# MCU.net
KiCad netlist of a schematic drawn in Altium Designer
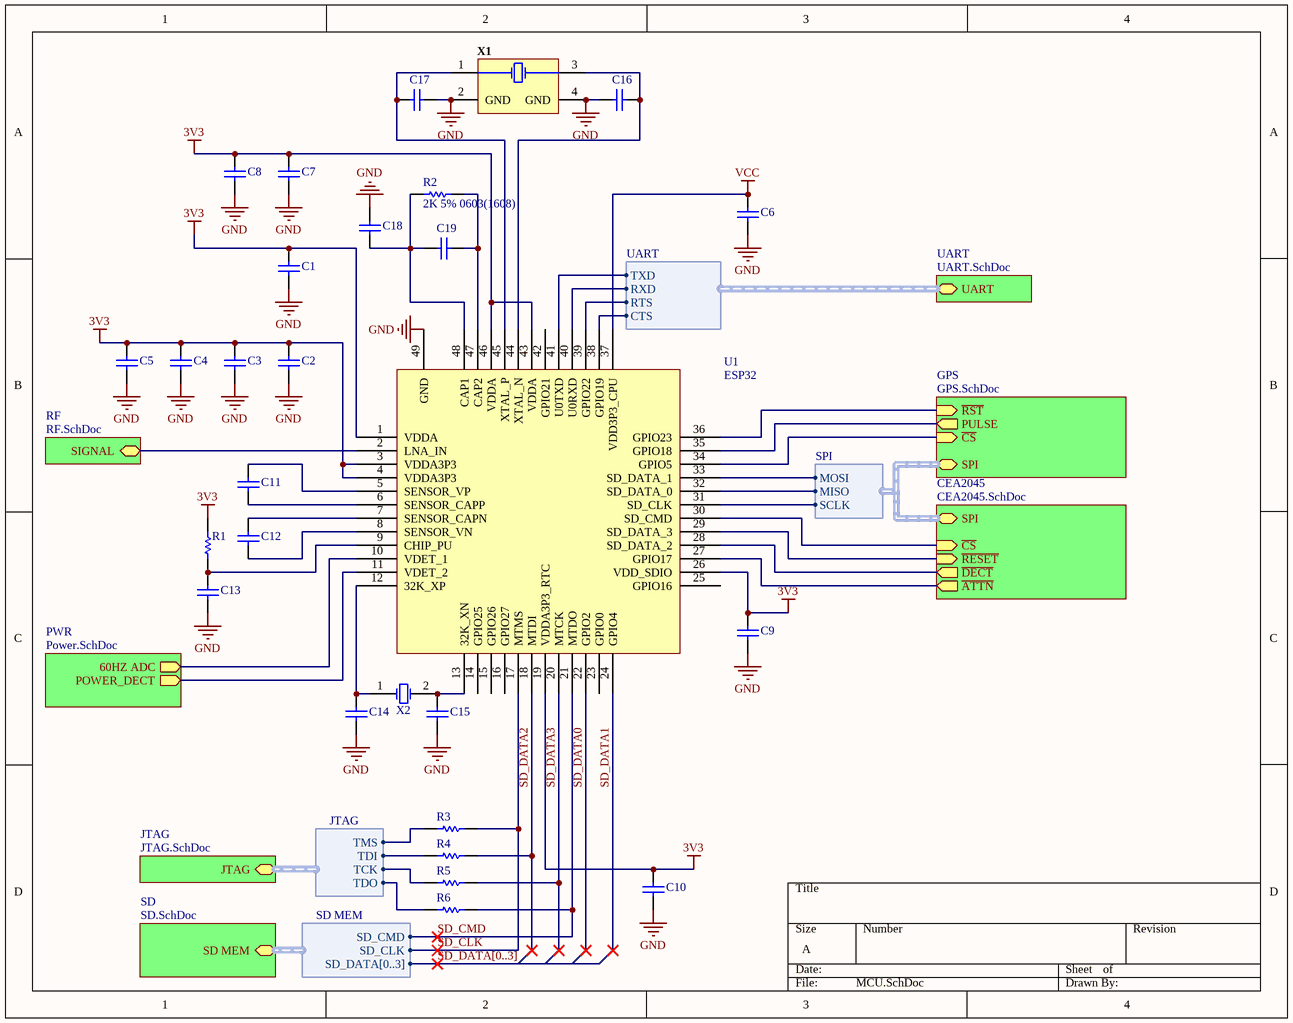
[diagram p0: MCU.SchDoc]

(export (version "E")
  (design (tool "Eeschema 10.0.6"))
  (components
    (comp (ref "C1")
      (value "CAP 100nF 6.3V 0603(1608)")
      (footprint "CAPC0603(1608)100_M")
      (description "CAP 100nF 6.3V ±5% 0603 (1608 Metric) Thickness 1mm SMD")
      (fields (field (name "TOLERANCE") "Â±5%"))
      (libsource (lib "Altium Content Vault") (part "CMP-1035-02575-1"))
    )
    (comp (ref "C2")
      (value "CAP 100nF 6.3V 0603(1608)")
      (footprint "CAPC0603(1608)100_M")
      (description "CAP 100nF 6.3V ±5% 0603 (1608 Metric) Thickness 1mm SMD")
      (fields (field (name "TOLERANCE") "Â±5%"))
      (libsource (lib "Altium Content Vault") (part "CMP-1035-02575-1"))
    )
    (comp (ref "C3")
      (value "CAP 10uF 6.3V 1210(3225)")
      (footprint "CAPC1210(3225)170_L")
      (description "CAP 10uF 6.3V ±10% 1210 (3225 Metric) Thickness 1.7mm SMD")
      (fields (field (name "TOLERANCE") "Â±10%"))
      (libsource (lib "Altium Content Vault") (part "CMP-1038-02188-1"))
    )
    (comp (ref "C4")
      (value "CAP 10uF 6.3V 1210(3225)")
      (footprint "CAPC1210(3225)170_L")
      (description "CAP 10uF 6.3V ±10% 1210 (3225 Metric) Thickness 1.7mm SMD")
      (fields (field (name "TOLERANCE") "Â±10%"))
      (libsource (lib "Altium Content Vault") (part "CMP-1038-02188-1"))
    )
    (comp (ref "C5")
      (value "CAP 1uF 6.3V 0603(1608)")
      (footprint "CAPC0603(1608)100_N")
      (description "CAP 1uF 6.3V ±10% 0603 (1608 Metric) Thickness 1mm SMD")
      (fields (field (name "TOLERANCE") "Â±10%"))
      (libsource (lib "Altium Content Vault") (part "CMP-1035-02730-1"))
    )
    (comp (ref "C6")
      (value "CAP 100nF 6.3V 0603(1608)")
      (footprint "CAPC0603(1608)100_M")
      (description "CAP 100nF 6.3V ±5% 0603 (1608 Metric) Thickness 1mm SMD")
      (fields (field (name "TOLERANCE") "Â±5%"))
      (libsource (lib "Altium Content Vault") (part "CMP-1035-02575-1"))
    )
    (comp (ref "C7")
      (value "CAP 1uF 6.3V 0603(1608)")
      (footprint "CAPC0603(1608)100_N")
      (description "CAP 1uF 6.3V ±10% 0603 (1608 Metric) Thickness 1mm SMD")
      (fields (field (name "TOLERANCE") "Â±10%"))
      (libsource (lib "Altium Content Vault") (part "CMP-1035-02730-1"))
    )
    (comp (ref "C8")
      (value "CAP 100pF 10V 0603(1608)")
      (footprint "CAPC0603(1608)100_N")
      (description "CAP 100pF 10V ±10% 0603 (1608 Metric) Thickness 1mm SMD")
      (fields (field (name "TOLERANCE") "Â±10%"))
      (libsource (lib "Altium Content Vault") (part "CMP-1035-01255-1"))
    )
    (comp (ref "C9")
      (value "CAP 1uF 6.3V 0603(1608)")
      (footprint "CAPC0603(1608)100_N")
      (description "CAP 1uF 6.3V ±10% 0603 (1608 Metric) Thickness 1mm SMD")
      (fields (field (name "TOLERANCE") "Â±10%"))
      (libsource (lib "Altium Content Vault") (part "CMP-1035-02730-1"))
    )
    (comp (ref "C10")
      (value "CAP 100nF 6.3V 0603(1608)")
      (footprint "CAPC0603(1608)100_M")
      (description "CAP 100nF 6.3V ±5% 0603 (1608 Metric) Thickness 1mm SMD")
      (fields (field (name "TOLERANCE") "Â±5%"))
      (libsource (lib "Altium Content Vault") (part "CMP-1035-02575-1"))
    )
    (comp (ref "C11")
      (value "CAP 220pF 6.3V 0603(1608)")
      (footprint "CAPC0603(1608)100_N")
      (description "CAP 220pF 6.3V ±10% 0603 (1608 Metric) Thickness 1mm SMD")
      (fields (field (name "TOLERANCE") "Â±10%"))
      (libsource (lib "Altium Content Vault") (part "CMP-1035-01452-1"))
    )
    (comp (ref "C12")
      (value "CAP 100nF 6.3V 0603(1608)")
      (footprint "CAPC0603(1608)100_M")
      (description "CAP 100nF 6.3V ±5% 0603 (1608 Metric) Thickness 1mm SMD")
      (fields (field (name "TOLERANCE") "Â±5%"))
      (libsource (lib "Altium Content Vault") (part "CMP-1035-02575-1"))
    )
    (comp (ref "C13")
      (value "CAP 100nF 6.3V 0603(1608)")
      (footprint "CAPC0603(1608)100_M")
      (description "CAP 100nF 6.3V ±5% 0603 (1608 Metric) Thickness 1mm SMD")
      (fields (field (name "TOLERANCE") "Â±5%"))
      (libsource (lib "Altium Content Vault") (part "CMP-1035-02575-1"))
    )
    (comp (ref "C14")
      (value "CAP 12pF 16V 0603(1608)")
      (footprint "CAPC0603(1608)100_M")
      (description "CAP 12pF 16V ±10% 0603 (1608 Metric) Thickness 1mm SMD")
      (fields (field (name "TOLERANCE") "Â±10%"))
      (libsource (lib "Altium Content Vault") (part "CMP-1035-00607-1"))
    )
    (comp (ref "C15")
      (value "CAP 12pF 16V 0603(1608)")
      (footprint "CAPC0603(1608)100_M")
      (description "CAP 12pF 16V ±10% 0603 (1608 Metric) Thickness 1mm SMD")
      (fields (field (name "TOLERANCE") "Â±10%"))
      (libsource (lib "Altium Content Vault") (part "CMP-1035-00607-1"))
    )
    (comp (ref "C16")
      (value "CAP 22pF 16V 0603(1608)")
      (footprint "CAPC0603(1608)100_M")
      (description "CAP 22pF 16V ±10% 0603 (1608 Metric) Thickness 1mm SMD")
      (fields (field (name "TOLERANCE") "Â±10%"))
      (libsource (lib "Altium Content Vault") (part "CMP-1035-00809-1"))
    )
    (comp (ref "C17")
      (value "CAP 10pF 10V 0603(1608)")
      (footprint "CAPC0603(1608)100_M")
      (description "CAP 10pF 10V ±10% 0603 (1608 Metric) Thickness 1mm SMD")
      (fields (field (name "TOLERANCE") "Â±10%"))
      (libsource (lib "Altium Content Vault") (part "CMP-1035-00539-1"))
    )
    (comp (ref "C18")
      (value "CAP 10nF 6.3V 0603(1608)")
      (footprint "CAPC0603(1608)100_M")
      (description "CAP 10nF 6.3V ±10% 0603 (1608 Metric) Thickness 1mm SMD")
      (fields (field (name "TOLERANCE") "Â±10%"))
      (libsource (lib "Altium Content Vault") (part "CMP-1035-02302-1"))
    )
    (comp (ref "C19")
      (value "CAP 3.3nF 6.3V 0603(1608)")
      (footprint "CAPC0603(1608)100_L")
      (description "CAP 3.3nF 6.3V ±10% 0603 (1608 Metric) Thickness 1mm SMD")
      (fields (field (name "TOLERANCE") "Â±10%"))
      (libsource (lib "Altium Content Vault") (part "CMP-1035-02104-1"))
    )
    (comp (ref "R1")
      (value "1K 5% 0603(1608)")
      (footprint "RESC0603(1608)_L")
      (description "1K 0.1W 5% 0603 (1608 Metric)  SMD")
      (fields (field (name "POWER") "0.1 W") (field (name "TOLERANCE") "5 %"))
      (libsource (lib "Altium Content Vault") (part "CMP-1012-00074-1"))
    )
    (comp (ref "R2")
      (value "2K 5% 0603(1608)")
      (footprint "RESC0603(1608)_N")
      (description "2K 0.1W 5% 0603 (1608 Metric)  SMD")
      (fields (field (name "TOLERANCE") "5 %") (field (name "POWER") "0.1 W"))
      (libsource (lib "Altium Content Vault") (part "RES"))
    )
    (comp (ref "R3")
      (value "100R 5% 0603(1608)")
      (footprint "RESC0603(1608)_L")
      (description "100R 0.1W 5% 0603 (1608 Metric)  SMD")
      (fields (field (name "POWER") "0.1 W") (field (name "TOLERANCE") "5 %"))
      (libsource (lib "Altium Content Vault") (part "CMP-1012-00050-1"))
    )
    (comp (ref "R4")
      (value "100R 5% 0603(1608)")
      (footprint "RESC0603(1608)_L")
      (description "100R 0.1W 5% 0603 (1608 Metric)  SMD")
      (fields (field (name "POWER") "0.1 W") (field (name "TOLERANCE") "5 %"))
      (libsource (lib "Altium Content Vault") (part "CMP-1012-00050-1"))
    )
    (comp (ref "R5")
      (value "100R 5% 0603(1608)")
      (footprint "RESC0603(1608)_L")
      (description "100R 0.1W 5% 0603 (1608 Metric)  SMD")
      (fields (field (name "POWER") "0.1 W") (field (name "TOLERANCE") "5 %"))
      (libsource (lib "Altium Content Vault") (part "CMP-1012-00050-1"))
    )
    (comp (ref "R6")
      (value "100R 5% 0603(1608)")
      (footprint "RESC0603(1608)_L")
      (description "100R 0.1W 5% 0603 (1608 Metric)  SMD")
      (fields (field (name "POWER") "0.1 W") (field (name "TOLERANCE") "5 %"))
      (libsource (lib "Altium Content Vault") (part "CMP-1012-00050-1"))
    )
    (comp (ref "U1")
      (value "ESP32")
      (footprint "QFN40P600X600X90_HS-49N")
      (libsource (lib "Water Heater Components") (part "ESP32"))
    )
    (comp (ref "X1")
      (value "7B-40.000MAAJ-T")
      (footprint "TXC-7B-4_V")
      (description "9B Series Quartz Crystal, 40 MHz, +/-30 ppm, 18 pF, -40 to 85 degC, 4-Pin SMD, RoHS, Tape and Reel")
      (fields (field (name "TOLERANCE") "1%"))
      (libsource (lib "Altium Content Vault") (part "CMP-1774-00003-1"))
    )
    (comp (ref "X2")
      (value "14340272-32.768KHz")
      (footprint "ITTI-14340272-32.768KHz-2_V")
      (description "Crystal, 32.768 KHz, -40 to 85 degC, 3.2 x 1.5 x 0.9 mm SMD")
      (fields (field (name "MANUFACTURER") "ITTI"))
      (libsource (lib "Altium Content Vault") (part "CMP-0463-00001-2"))
    )
  )
  (nets
    (net (code "5") (name "/60HZ ADC") (class "Default")
      (node (ref "U1") (pin "10") (pinfunction "VDET_1_10") (pintype "passive"))
    )
    (net (code "6") (name "/CTS") (class "Default")
      (node (ref "U1") (pin "38") (pinfunction "GPIO19_38") (pintype "passive"))
    )
    (net (code "7") (name "/MISO") (class "Default")
      (node (ref "U1") (pin "32") (pinfunction "SD_DATA_0_32") (pintype "passive"))
    )
    (net (code "8") (name "/MOSI") (class "Default")
      (node (ref "U1") (pin "33") (pinfunction "SD_DATA_1_33") (pintype "passive"))
    )
    (net (code "9") (name "/POWER_DECT") (class "Default")
      (node (ref "U1") (pin "11") (pinfunction "VDET_2_11") (pintype "passive"))
    )
    (net (code "10") (name "/PULSE") (class "Default")
      (node (ref "U1") (pin "35") (pinfunction "GPIO18_35") (pintype "passive"))
    )
    (net (code "11") (name "/RTS") (class "Default")
      (node (ref "U1") (pin "39") (pinfunction "GPIO22_39") (pintype "passive"))
    )
    (net (code "12") (name "/RXD") (class "Default")
      (node (ref "U1") (pin "40") (pinfunction "U0RXD_40") (pintype "passive"))
    )
    (net (code "13") (name "/SCLK") (class "Default")
      (node (ref "U1") (pin "31") (pinfunction "SD_CLK_31") (pintype "passive"))
    )
    (net (code "17") (name "/SD_DATA0") (class "Default")
      (node (ref "U1") (pin "22") (pinfunction "GPIO2_22") (pintype "passive+no_connect"))
    )
    (net (code "18") (name "/SD_DATA1") (class "Default")
      (node (ref "U1") (pin "24") (pinfunction "GPIO4_24") (pintype "passive+no_connect"))
    )
    (net (code "19") (name "/SD_DATA2") (class "Default")
      (node (ref "R4") (pin "2") (pinfunction "2_2") (pintype "passive"))
      (node (ref "U1") (pin "18") (pinfunction "MTDI_18") (pintype "passive"))
    )
    (net (code "20") (name "/SD_DATA3") (class "Default")
      (node (ref "R5") (pin "2") (pinfunction "2_2") (pintype "passive"))
      (node (ref "U1") (pin "20") (pinfunction "MTCK_20") (pintype "passive"))
    )
    (net (code "21") (name "/SIGNAL") (class "Default")
      (node (ref "U1") (pin "2") (pinfunction "LNA_IN_2") (pintype "passive"))
    )
    (net (code "22") (name "/TCK") (class "Default")
      (node (ref "R5") (pin "1") (pinfunction "1_1") (pintype "passive"))
    )
    (net (code "23") (name "/TDI") (class "Default")
      (node (ref "R4") (pin "1") (pinfunction "1_1") (pintype "passive"))
    )
    (net (code "24") (name "/TDO") (class "Default")
      (node (ref "R6") (pin "1") (pinfunction "1_1") (pintype "passive"))
    )
    (net (code "25") (name "/TMS") (class "Default")
      (node (ref "R3") (pin "1") (pinfunction "1_1") (pintype "passive"))
    )
    (net (code "26") (name "/TXD") (class "Default")
      (node (ref "U1") (pin "41") (pinfunction "U0TXD_41") (pintype "passive"))
    )
    (net (code "31") (name "/~{ATTN}") (class "Default")
      (node (ref "U1") (pin "27") (pinfunction "GPIO17_27") (pintype "passive"))
    )
    (net (code "32") (name "/~{CS}") (class "Default")
      (node (ref "U1") (pin "34") (pinfunction "GPIO5_34") (pintype "passive"))
    )
    (net (code "33") (name "/~{CS}_1") (class "Default")
      (node (ref "U1") (pin "30") (pinfunction "SD_CMD_30") (pintype "passive"))
    )
    (net (code "34") (name "/~{DECT}") (class "Default")
      (node (ref "U1") (pin "28") (pinfunction "SD_DATA_2_28") (pintype "passive"))
    )
    (net (code "35") (name "/~{RESET}") (class "Default")
      (node (ref "U1") (pin "29") (pinfunction "SD_DATA_3_29") (pintype "passive"))
    )
    (net (code "36") (name "/~{RST}") (class "Default")
      (node (ref "U1") (pin "36") (pinfunction "GPIO23_36") (pintype "passive"))
    )
    (net (code "37") (name "3V3") (class "Default")
      (node (ref "C1") (pin "2") (pinfunction "2_2") (pintype "passive"))
      (node (ref "C10") (pin "2") (pinfunction "2_2") (pintype "passive"))
      (node (ref "C2") (pin "2") (pinfunction "2_2") (pintype "passive"))
      (node (ref "C3") (pin "2") (pinfunction "2_2") (pintype "passive"))
      (node (ref "C4") (pin "2") (pinfunction "2_2") (pintype "passive"))
      (node (ref "C5") (pin "1") (pinfunction "1_1") (pintype "passive"))
      (node (ref "C7") (pin "1") (pinfunction "1_1") (pintype "passive"))
      (node (ref "C8") (pin "2") (pinfunction "2_2") (pintype "passive"))
      (node (ref "C9") (pin "1") (pinfunction "1_1") (pintype "passive"))
      (node (ref "R1") (pin "2") (pinfunction "2_2") (pintype "passive"))
      (node (ref "U1") (pin "1") (pinfunction "VDDA_1") (pintype "passive"))
      (node (ref "U1") (pin "19") (pinfunction "VDDA3P3_RTC_19") (pintype "passive"))
      (node (ref "U1") (pin "26") (pinfunction "VDD_SDIO_26") (pintype "passive"))
      (node (ref "U1") (pin "3") (pinfunction "VDDA3P3_3") (pintype "passive"))
      (node (ref "U1") (pin "4") (pinfunction "VDDA3P3_4") (pintype "passive"))
      (node (ref "U1") (pin "43") (pinfunction "VDDA_43") (pintype "passive"))
      (node (ref "U1") (pin "46") (pinfunction "VDDA_46") (pintype "passive"))
    )
    (net (code "38") (name "GND") (class "Default")
      (node (ref "C1") (pin "1") (pinfunction "1_1") (pintype "passive"))
      (node (ref "C10") (pin "1") (pinfunction "1_1") (pintype "passive"))
      (node (ref "C13") (pin "1") (pinfunction "1_1") (pintype "passive"))
      (node (ref "C14") (pin "1") (pinfunction "1_1") (pintype "passive"))
      (node (ref "C15") (pin "1") (pinfunction "1_1") (pintype "passive"))
      (node (ref "C16") (pin "1") (pinfunction "1_1") (pintype "passive"))
      (node (ref "C17") (pin "1") (pinfunction "1_1") (pintype "passive"))
      (node (ref "C18") (pin "2") (pinfunction "2_2") (pintype "passive"))
      (node (ref "C2") (pin "1") (pinfunction "1_1") (pintype "passive"))
      (node (ref "C3") (pin "1") (pinfunction "1_1") (pintype "passive"))
      (node (ref "C4") (pin "1") (pinfunction "1_1") (pintype "passive"))
      (node (ref "C5") (pin "2") (pinfunction "2_2") (pintype "passive"))
      (node (ref "C6") (pin "1") (pinfunction "1_1") (pintype "passive"))
      (node (ref "C7") (pin "2") (pinfunction "2_2") (pintype "passive"))
      (node (ref "C8") (pin "1") (pinfunction "1_1") (pintype "passive"))
      (node (ref "C9") (pin "2") (pinfunction "2_2") (pintype "passive"))
      (node (ref "U1") (pin "49") (pinfunction "GND_49") (pintype "passive"))
      (node (ref "X1") (pin "2") (pinfunction "GND_2") (pintype "power_in"))
      (node (ref "X1") (pin "4") (pinfunction "GND_4") (pintype "power_in"))
    )
    (net (code "39") (name "Net-(U1-32K_XN)") (class "Default")
      (node (ref "C15") (pin "2") (pinfunction "2_2") (pintype "passive"))
      (node (ref "U1") (pin "13") (pinfunction "32K_XN_13") (pintype "passive"))
      (node (ref "X2") (pin "2") (pinfunction "X2_2") (pintype "passive"))
    )
    (net (code "40") (name "Net-(U1-32K_XP)") (class "Default")
      (node (ref "C14") (pin "2") (pinfunction "2_2") (pintype "passive"))
      (node (ref "U1") (pin "12") (pinfunction "32K_XP_12") (pintype "passive"))
      (node (ref "X2") (pin "1") (pinfunction "X1_1") (pintype "passive"))
    )
    (net (code "41") (name "Net-(U1-CAP1)") (class "Default")
      (node (ref "C18") (pin "1") (pinfunction "1_1") (pintype "passive"))
      (node (ref "C19") (pin "1") (pinfunction "1_1") (pintype "passive"))
      (node (ref "R2") (pin "1") (pinfunction "1_1") (pintype "passive"))
      (node (ref "U1") (pin "48") (pinfunction "CAP1_48") (pintype "passive"))
    )
    (net (code "42") (name "Net-(U1-CAP2)") (class "Default")
      (node (ref "C19") (pin "2") (pinfunction "2_2") (pintype "passive"))
      (node (ref "R2") (pin "2") (pinfunction "2_2") (pintype "passive"))
      (node (ref "U1") (pin "47") (pinfunction "CAP2_47") (pintype "passive"))
    )
    (net (code "43") (name "Net-(U1-CHIP_PU)") (class "Default")
      (node (ref "C13") (pin "2") (pinfunction "2_2") (pintype "passive"))
      (node (ref "R1") (pin "1") (pinfunction "1_1") (pintype "passive"))
      (node (ref "U1") (pin "9") (pinfunction "CHIP_PU_9") (pintype "passive"))
    )
    (net (code "44") (name "Net-(U1-MTDO)") (class "Default")
      (node (ref "R6") (pin "2") (pinfunction "2_2") (pintype "passive"))
      (node (ref "U1") (pin "21") (pinfunction "MTDO_21") (pintype "passive"))
    )
    (net (code "45") (name "Net-(U1-MTMS)") (class "Default")
      (node (ref "R3") (pin "2") (pinfunction "2_2") (pintype "passive"))
      (node (ref "U1") (pin "17") (pinfunction "MTMS_17") (pintype "passive"))
    )
    (net (code "46") (name "Net-(U1-SENSOR_CAPN)") (class "Default")
      (node (ref "C12") (pin "2") (pinfunction "2_2") (pintype "passive"))
      (node (ref "U1") (pin "7") (pinfunction "SENSOR_CAPN_7") (pintype "passive"))
    )
    (net (code "47") (name "Net-(U1-SENSOR_CAPP)") (class "Default")
      (node (ref "C11") (pin "1") (pinfunction "1_1") (pintype "passive"))
      (node (ref "U1") (pin "6") (pinfunction "SENSOR_CAPP_6") (pintype "passive"))
    )
    (net (code "48") (name "Net-(U1-SENSOR_VN)") (class "Default")
      (node (ref "C12") (pin "1") (pinfunction "1_1") (pintype "passive"))
      (node (ref "U1") (pin "8") (pinfunction "SENSOR_VN_8") (pintype "passive"))
    )
    (net (code "49") (name "Net-(U1-SENSOR_VP)") (class "Default")
      (node (ref "C11") (pin "2") (pinfunction "2_2") (pintype "passive"))
      (node (ref "U1") (pin "5") (pinfunction "SENSOR_VP_5") (pintype "passive"))
    )
    (net (code "50") (name "Net-(U1-XTAL_N)") (class "Default")
      (node (ref "C16") (pin "2") (pinfunction "2_2") (pintype "passive"))
      (node (ref "U1") (pin "44") (pinfunction "XTAL_N_44") (pintype "passive"))
      (node (ref "X1") (pin "3") (pinfunction "X2_3") (pintype "passive"))
    )
    (net (code "51") (name "Net-(U1-XTAL_P)") (class "Default")
      (node (ref "C17") (pin "2") (pinfunction "2_2") (pintype "passive"))
      (node (ref "U1") (pin "45") (pinfunction "XTAL_P_45") (pintype "passive"))
      (node (ref "X1") (pin "1") (pinfunction "X1_1") (pintype "passive"))
    )
    (net (code "52") (name "VCC") (class "Default")
      (node (ref "C6") (pin "2") (pinfunction "2_2") (pintype "passive"))
      (node (ref "U1") (pin "37") (pinfunction "VDD3P3_CPU_37") (pintype "passive"))
    )
    (net (code "53") (name "unconnected-(U1-GPIO0-Pad23)") (class "Default")
      (node (ref "U1") (pin "23") (pinfunction "GPIO0_23") (pintype "passive"))
    )
    (net (code "54") (name "unconnected-(U1-GPIO16-Pad25)") (class "Default")
      (node (ref "U1") (pin "25") (pinfunction "GPIO16_25") (pintype "passive"))
    )
    (net (code "55") (name "unconnected-(U1-GPIO21-Pad42)") (class "Default")
      (node (ref "U1") (pin "42") (pinfunction "GPIO21_42") (pintype "passive"))
    )
    (net (code "56") (name "unconnected-(U1-GPIO25-Pad14)") (class "Default")
      (node (ref "U1") (pin "14") (pinfunction "GPIO25_14") (pintype "passive"))
    )
    (net (code "57") (name "unconnected-(U1-GPIO26-Pad15)") (class "Default")
      (node (ref "U1") (pin "15") (pinfunction "GPIO26_15") (pintype "passive"))
    )
    (net (code "58") (name "unconnected-(U1-GPIO27-Pad16)") (class "Default")
      (node (ref "U1") (pin "16") (pinfunction "GPIO27_16") (pintype "passive"))
    )
  )
)
